# power.net
KiCad netlist of a schematic drawn in Altium Designer
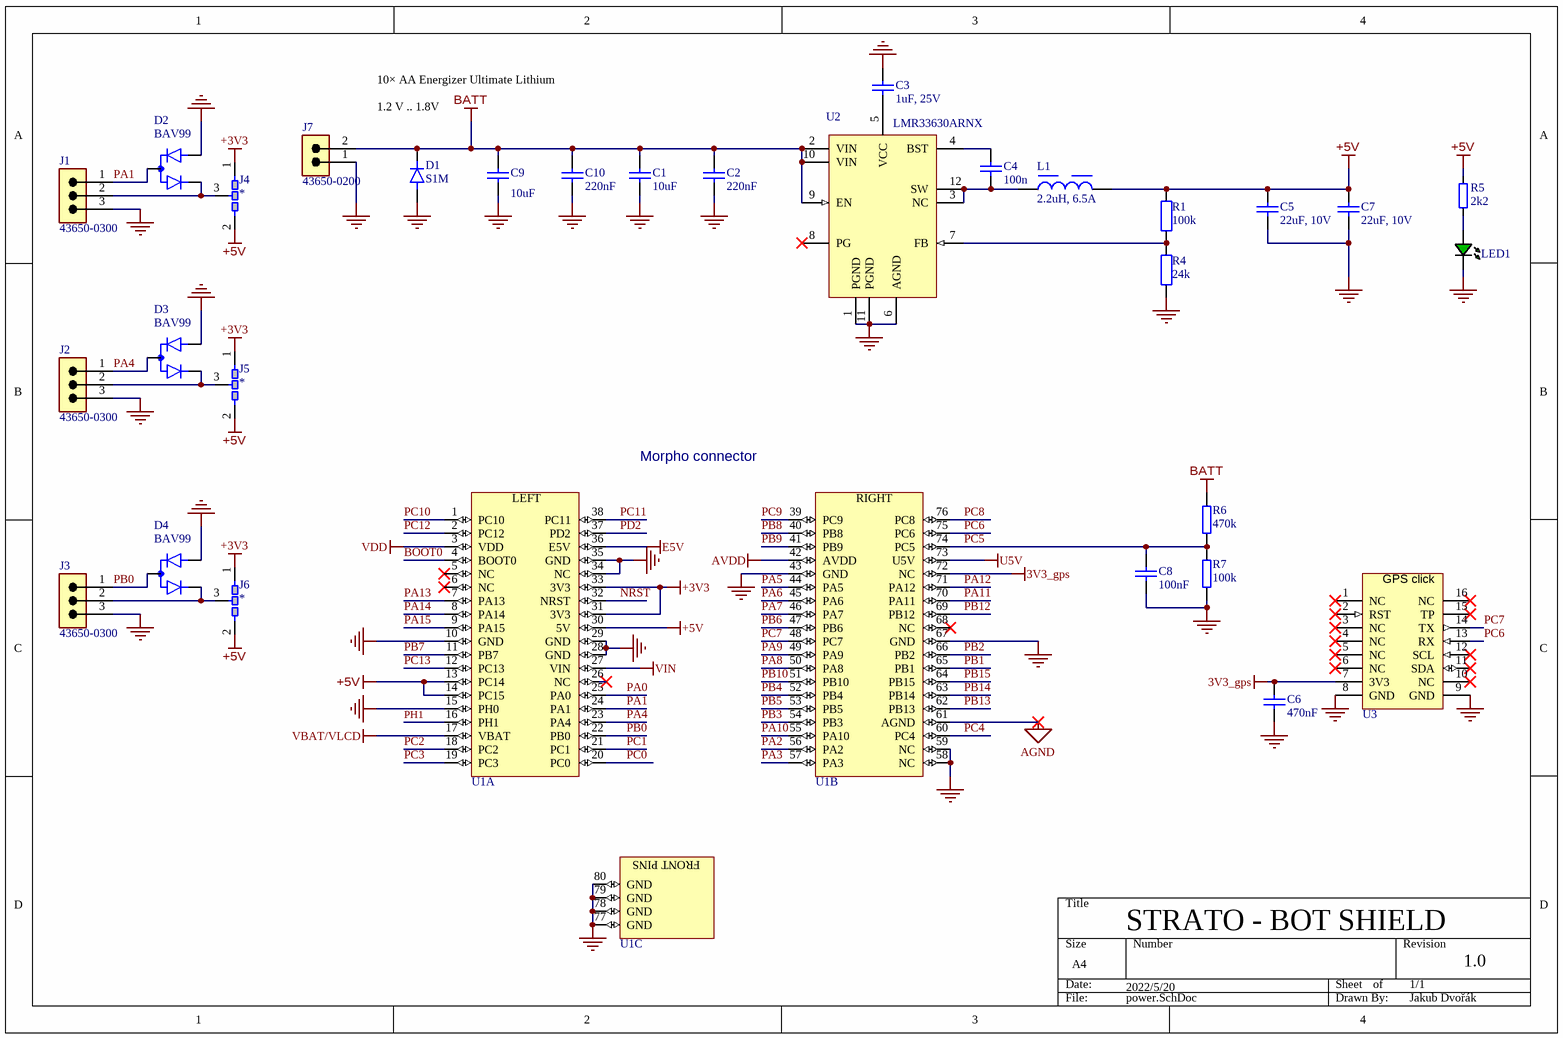
[diagram p0: power.SchDoc]

(export (version "E")
  (design (tool "Eeschema 10.0.6"))
  (components
    (comp (ref "C1")
      (value "10uF")
      (footprint "WCAP-CSGP_1206_L3.2W1.6H1.6")
      (description "WCAP-CSGP Multilayer Ceramic Chip Capacitor, General Purpose, size 1206, X5R, 10uF, 50V")
      (fields
        (field (name "MANUFACTURER") "Wurth Elektronik")
        (field (name "MANUFACTURER PART NUMBER") "885012108022")
      )
      (libsource (lib "Altium_WCAP-CSGP (rev22a)") (part "885012108022"))
    )
    (comp (ref "C2")
      (value "220nF")
      (footprint "WCAP-CSGP_0603_L1.6W0.8H0.8_Reflow")
      (description "WCAP-CSGP Multilayer Ceramic Chip Capacitor, General Purpose, size 0603, X7R, 220nF, 50V")
      (fields
        (field (name "MANUFACTURER") "Wurth Elektronik")
        (field (name "MANUFACTURER PART NUMBER") "885012206125")
      )
      (libsource (lib "Altium_WCAP-CSGP (rev22a)") (part "885012206125"))
    )
    (comp (ref "C3")
      (value "1uF, 25V")
      (footprint "WCAP-CSGP_0603_L1.6W0.8H0.8_Reflow")
      (description "WCAP-CSGP Multilayer Ceramic Chip Capacitor, General Purpose, size 0603, X7R, 1uF, 25V")
      (fields
        (field (name "MANUFACTURER") "Wurth Elektronik")
        (field (name "MANUFACTURER PART NUMBER") "885012206076")
      )
      (libsource (lib "Altium_WCAP-CSGP (rev22a)") (part "885012206076"))
    )
    (comp (ref "C4")
      (value "100n")
      (footprint "WCAP-CSGP_0603_L1.6W0.8H0.8_Reflow")
      (description "WCAP-CSGP Multilayer Ceramic Chip Capacitor, General Purpose, size 0603, X7R, 100nF, 25V")
      (fields
        (field (name "MANUFACTURER") "Wurth Elektronik")
        (field (name "MANUFACTURER PART NUMBER") "885012206071R")
      )
      (libsource (lib "Altium_WCAP-CSGP (rev22a)") (part "885012206071R"))
    )
    (comp (ref "C5")
      (value "22uF, 10V")
      (footprint "WCAP-CSGP_0805_L2W1.25H1.25")
      (description "WCAP-CSGP Multilayer Ceramic Chip Capacitor, General Purpose, size 0805, X5R, 22uF, 10V")
      (fields
        (field (name "MANUFACTURER") "Wurth Elektronik")
        (field (name "MANUFACTURER PART NUMBER") "885012107011")
      )
      (libsource (lib "Altium_WCAP-CSGP (rev22a)") (part "885012107011"))
    )
    (comp (ref "C6")
      (value "470nF")
      (footprint "WCAP-CSGP_0805_L2W1.25H1.25")
      (description "WCAP-CSGP Multilayer Ceramic Chip Capacitor, General Purpose, size 0805, X7R, 470nF, 50V")
      (fields
        (field (name "MANUFACTURER") "Wurth Elektronik")
        (field (name "MANUFACTURER PART NUMBER") "885012207102")
      )
      (libsource (lib "Altium_WCAP-CSGP (rev22a)") (part "885012207102"))
    )
    (comp (ref "C7")
      (value "22uF, 10V")
      (footprint "WCAP-CSGP_0805_L2W1.25H1.25")
      (description "WCAP-CSGP Multilayer Ceramic Chip Capacitor, General Purpose, size 0805, X5R, 22uF, 10V")
      (fields
        (field (name "MANUFACTURER") "Wurth Elektronik")
        (field (name "MANUFACTURER PART NUMBER") "885012107011")
      )
      (libsource (lib "Altium_WCAP-CSGP (rev22a)") (part "885012107011"))
    )
    (comp (ref "C8")
      (value "100nF")
      (footprint "WCAP-CSGP_0805_L2W1.25H0.8_Reflow")
      (description "WCAP-CSGP Multilayer Ceramic Chip Capacitor, General Purpose, size 0805, X7R, 100nF, 50V")
      (fields
        (field (name "MANUFACTURER") "Wurth Elektronik")
        (field (name "MANUFACTURER PART NUMBER") "885012207098R")
      )
      (libsource (lib "Altium_WCAP-CSGP (rev22a)") (part "885012207098R"))
    )
    (comp (ref "C9")
      (value "10uF")
      (footprint "WCAP-CSGP_1206_L3.2W1.6H1.6")
      (description "WCAP-CSGP Multilayer Ceramic Chip Capacitor, General Purpose, size 1206, X5R, 10uF, 50V")
      (fields
        (field (name "MANUFACTURER") "Wurth Elektronik")
        (field (name "MANUFACTURER PART NUMBER") "885012108022")
      )
      (libsource (lib "Altium_WCAP-CSGP (rev22a)") (part "885012108022"))
    )
    (comp (ref "C10")
      (value "220nF")
      (footprint "WCAP-CSGP_0603_L1.6W0.8H0.8_Reflow")
      (description "WCAP-CSGP Multilayer Ceramic Chip Capacitor, General Purpose, size 0603, X7R, 220nF, 50V")
      (fields
        (field (name "MANUFACTURER") "Wurth Elektronik")
        (field (name "MANUFACTURER PART NUMBER") "885012206125")
      )
      (libsource (lib "Altium_WCAP-CSGP (rev22a)") (part "885012206125"))
    )
    (comp (ref "D1")
      (value "S1M")
      (footprint "DIOM5127X23N(SMA)")
      (description "D; Si; 1000V; 1A; 1x;")
      (libsource (lib "altium_sql") (part "D"))
    )
    (comp (ref "D2")
      (value "BAV99")
      (footprint "SOT95P230X110-3N(SOT23)")
      (libsource (lib "Kubikova integrovana knihovna ") (part "BAV99"))
    )
    (comp (ref "D3")
      (value "BAV99")
      (footprint "SOT95P230X110-3N(SOT23)")
      (libsource (lib "Kubikova integrovana knihovna ") (part "BAV99"))
    )
    (comp (ref "D4")
      (value "BAV99")
      (footprint "SOT95P230X110-3N(SOT23)")
      (libsource (lib "Kubikova integrovana knihovna ") (part "BAV99"))
    )
    (comp (ref "J1")
      (value "43650-0300")
      (footprint "MOLEX_43650-0300")
      (description "Con; Micro Fit 3.0; 3x; PCB; Right angle; 250V; 5A; Male; Tin; ??;")
      (fields (field (name "MANUFACTURER") "Molex: 436500300"))
      (libsource (lib "altium_sql") (part "EJ_3PIN_MALE"))
    )
    (comp (ref "J2")
      (value "43650-0300")
      (footprint "MOLEX_43650-0300")
      (description "Con; Micro Fit 3.0; 3x; PCB; Right angle; 250V; 5A; Male; Tin; ??;")
      (fields (field (name "MANUFACTURER") "Molex: 436500300"))
      (libsource (lib "altium_sql") (part "EJ_3PIN_MALE"))
    )
    (comp (ref "J3")
      (value "43650-0300")
      (footprint "MOLEX_43650-0300")
      (description "Con; Micro Fit 3.0; 3x; PCB; Right angle; 250V; 5A; Male; Tin; ??;")
      (fields (field (name "MANUFACTURER") "Molex: 436500300"))
      (libsource (lib "altium_sql") (part "EJ_3PIN_MALE"))
    )
    (comp (ref "J4")
      (value "*")
      (footprint "JUMPER3_SMT_1LAYER")
      (description "Soldering Jumper, 3 Pins")
      (fields (field (name "AUTHOR") "JM 1.9.2015"))
      (libsource (lib "Production_Library") (part "JUMPER_3P"))
    )
    (comp (ref "J5")
      (value "*")
      (footprint "JUMPER3_SMT_1LAYER")
      (description "Soldering Jumper, 3 Pins")
      (fields (field (name "AUTHOR") "JM 1.9.2015"))
      (libsource (lib "Production_Library") (part "JUMPER_3P"))
    )
    (comp (ref "J6")
      (value "*")
      (footprint "JUMPER3_SMT_1LAYER")
      (description "Soldering Jumper, 3 Pins")
      (fields (field (name "AUTHOR") "JM 1.9.2015"))
      (libsource (lib "Production_Library") (part "JUMPER_3P"))
    )
    (comp (ref "J7")
      (value "43650-0200")
      (footprint "MOLEX_43650-0200")
      (description "Con; Micro Fit 3.0; 2x; PCB; Right angle; 600V; 5A; Male; Nickel; ??;")
      (fields (field (name "MANUFACTURER") "MOLEX: 43650-0200"))
      (libsource (lib "altium_sql") (part "EJ_2PIN_MALE"))
    )
    (comp (ref "L1")
      (value "2.2uH, 6.5A")
      (footprint "WE-LHMI_7030")
      (description "WE-LHMI SMT Power Inductor, size 7030, 2.2uH, 6.5A")
      (fields
        (field (name "MANUFACTURER") "Wurth Elektronik")
        (field (name "MANUFACTURER PART NUMBER") "74437346022")
      )
      (libsource (lib "ind-WE-LHMI (rev21a)") (part "74437346022"))
    )
    (comp (ref "LED1")
      (value "green")
      (footprint "0805LEDG")
      (libsource (lib "all_in_one_library") (part "LEDG_0805"))
    )
    (comp (ref "R1")
      (value "100k")
      (footprint "RES_0603")
      (description "100000.00")
      (fields (field (name "Comment") "Thick film"))
      (libsource (lib "all_in_one_library") (part "RES_100k_5%_0603"))
    )
    (comp (ref "R4")
      (value "24k")
      (footprint "RES_0603")
      (description "24000.00")
      (fields (field (name "Comment") "Thick film"))
      (libsource (lib "all_in_one_library") (part "RES_24k_5%_0603"))
    )
    (comp (ref "R5")
      (value "2k2")
      (footprint "RES_0603")
      (description "2200.00")
      (fields (field (name "Comment") "Thick film"))
      (libsource (lib "all_in_one_library") (part "RES_2k2_5%_0603"))
    )
    (comp (ref "R6")
      (value "470k")
      (footprint "RESC2012X06N(SMR0805)")
      (description "R; 470k; 0.125W; 1%; 150V; Thick Film; ±100ppm/K; 1x;")
      (libsource (lib "altium_sql") (part "R"))
    )
    (comp (ref "R7")
      (value "100k")
      (footprint "RESC2012X06N(SMR0805)")
      (description "R; 100k; 0.125W; 1%; 150V; Thick Film; ±100ppm/K; 1x;")
      (fields (field (name "MANUFACTURER") "YAGEO: RC0805FR-10100KL"))
      (libsource (lib "altium_sql") (part "R"))
    )
    (comp (ref "U1")
      (value "NUCLEO F466 MORPHO LEFT")
      (footprint "Nucleo_bot_pads")
      (libsource (lib "Kubikova ultra knihovna") (part "NUCLEO F466 MORPHO LEFT"))
    )
    (comp (ref "U2")
      (value "LMR33630ARNX")
      (footprint "QFN50P200X300X100-12N")
      (description "IC; SMPS Regulator/Controller; 3.8V; 36V; 1x;")
      (fields
        (field (name "MANUFACTURER") "Texas Instruments: LMR33630ARNXR;;Texas Instruments: LMR33630ARNXT")
      )
      (libsource (lib "altium_sql") (part "EU+LMR33630ARNXXX0"))
    )
    (comp (ref "U3")
      (value "GPS Click")
      (footprint "GPS click - no legs")
      (libsource (lib "Kubikova ultra knihovna") (part "GPS Click"))
    )
  )
  (nets
    (net (code "1") (name "+3V3") (class "Default")
      (node (ref "J4") (pin "1") (pinfunction "1_1") (pintype "passive"))
      (node (ref "J5") (pin "1") (pinfunction "1_1") (pintype "passive"))
      (node (ref "J6") (pin "1") (pinfunction "1_1") (pintype "passive"))
      (node (ref "U1") (pin "31") (pinfunction "3V3_31") (pintype "bidirectional"))
      (node (ref "U1") (pin "33") (pinfunction "3V3_33") (pintype "bidirectional"))
    )
    (net (code "2") (name "+5V") (class "Default")
      (node (ref "C5") (pin "2") (pinfunction "2_2") (pintype "passive"))
      (node (ref "C7") (pin "2") (pinfunction "2_2") (pintype "passive"))
      (node (ref "J4") (pin "2") (pinfunction "2_2") (pintype "passive"))
      (node (ref "J5") (pin "2") (pinfunction "2_2") (pintype "passive"))
      (node (ref "J6") (pin "2") (pinfunction "2_2") (pintype "passive"))
      (node (ref "L1") (pin "2") (pinfunction "2_2") (pintype "passive"))
      (node (ref "R1") (pin "2") (pinfunction "2_2") (pintype "passive"))
      (node (ref "R5") (pin "2") (pinfunction "2_2") (pintype "passive"))
      (node (ref "U1") (pin "13") (pinfunction "PC14_13") (pintype "bidirectional"))
      (node (ref "U1") (pin "14") (pinfunction "PC15_14") (pintype "bidirectional"))
      (node (ref "U1") (pin "30") (pinfunction "5V_30") (pintype "bidirectional"))
    )
    (net (code "3") (name "/BOOT0") (class "Default")
      (node (ref "U1") (pin "4") (pinfunction "BOOT0_4") (pintype "bidirectional"))
    )
    (net (code "4") (name "/NRST") (class "Default")
      (node (ref "U1") (pin "32") (pinfunction "NRST_32") (pintype "bidirectional"))
    )
    (net (code "5") (name "/PA0") (class "Default")
      (node (ref "U1") (pin "25") (pinfunction "PA0_25") (pintype "bidirectional"))
    )
    (net (code "6") (name "/PA1") (class "Default")
      (node (ref "D2") (pin "3") (pinfunction "C1A2_3") (pintype "passive"))
      (node (ref "J1") (pin "1") (pinfunction "1_1") (pintype "passive"))
      (node (ref "U1") (pin "24") (pinfunction "PA1_24") (pintype "bidirectional"))
    )
    (net (code "7") (name "/PA2") (class "Default")
      (node (ref "U1") (pin "56") (pinfunction "PA2_56") (pintype "bidirectional"))
    )
    (net (code "8") (name "/PA3") (class "Default")
      (node (ref "U1") (pin "57") (pinfunction "PA3_57") (pintype "bidirectional"))
    )
    (net (code "9") (name "/PA4") (class "Default")
      (node (ref "D3") (pin "3") (pinfunction "C1A2_3") (pintype "passive"))
      (node (ref "J2") (pin "1") (pinfunction "1_1") (pintype "passive"))
      (node (ref "U1") (pin "23") (pinfunction "PA4_23") (pintype "bidirectional"))
    )
    (net (code "10") (name "/PA5") (class "Default")
      (node (ref "U1") (pin "44") (pinfunction "PA5_44") (pintype "bidirectional"))
    )
    (net (code "11") (name "/PA6") (class "Default")
      (node (ref "U1") (pin "45") (pinfunction "PA6_45") (pintype "bidirectional"))
    )
    (net (code "12") (name "/PA7") (class "Default")
      (node (ref "U1") (pin "46") (pinfunction "PA7_46") (pintype "bidirectional"))
    )
    (net (code "13") (name "/PA8") (class "Default")
      (node (ref "U1") (pin "50") (pinfunction "PA8_50") (pintype "bidirectional"))
    )
    (net (code "14") (name "/PA9") (class "Default")
      (node (ref "U1") (pin "49") (pinfunction "PA9_49") (pintype "bidirectional"))
    )
    (net (code "15") (name "/PA10") (class "Default")
      (node (ref "U1") (pin "55") (pinfunction "PA10_55") (pintype "bidirectional"))
    )
    (net (code "16") (name "/PA11") (class "Default")
      (node (ref "U1") (pin "70") (pinfunction "PA11_70") (pintype "bidirectional"))
    )
    (net (code "17") (name "/PA12") (class "Default")
      (node (ref "U1") (pin "71") (pinfunction "PA12_71") (pintype "bidirectional"))
    )
    (net (code "18") (name "/PA13") (class "Default")
      (node (ref "U1") (pin "7") (pinfunction "PA13_7") (pintype "bidirectional"))
    )
    (net (code "19") (name "/PA14") (class "Default")
      (node (ref "U1") (pin "8") (pinfunction "PA14_8") (pintype "bidirectional"))
    )
    (net (code "20") (name "/PA15") (class "Default")
      (node (ref "U1") (pin "9") (pinfunction "PA15_9") (pintype "bidirectional"))
    )
    (net (code "21") (name "/PB0") (class "Default")
      (node (ref "D4") (pin "3") (pinfunction "C1A2_3") (pintype "passive"))
      (node (ref "J3") (pin "1") (pinfunction "1_1") (pintype "passive"))
      (node (ref "U1") (pin "22") (pinfunction "PB0_22") (pintype "bidirectional"))
    )
    (net (code "22") (name "/PB1") (class "Default")
      (node (ref "U1") (pin "65") (pinfunction "PB1_65") (pintype "bidirectional"))
    )
    (net (code "23") (name "/PB2") (class "Default")
      (node (ref "U1") (pin "66") (pinfunction "PB2_66") (pintype "bidirectional"))
    )
    (net (code "24") (name "/PB3") (class "Default")
      (node (ref "U1") (pin "54") (pinfunction "PB3_54") (pintype "bidirectional"))
    )
    (net (code "25") (name "/PB4") (class "Default")
      (node (ref "U1") (pin "52") (pinfunction "PB4_52") (pintype "bidirectional"))
    )
    (net (code "26") (name "/PB5") (class "Default")
      (node (ref "U1") (pin "53") (pinfunction "PB5_53") (pintype "bidirectional"))
    )
    (net (code "27") (name "/PB6") (class "Default")
      (node (ref "U1") (pin "47") (pinfunction "PB6_47") (pintype "bidirectional"))
    )
    (net (code "28") (name "/PB7") (class "Default")
      (node (ref "U1") (pin "11") (pinfunction "PB7_11") (pintype "bidirectional"))
    )
    (net (code "29") (name "/PB8") (class "Default")
      (node (ref "U1") (pin "40") (pinfunction "PB8_40") (pintype "bidirectional"))
    )
    (net (code "30") (name "/PB9") (class "Default")
      (node (ref "U1") (pin "41") (pinfunction "PB9_41") (pintype "bidirectional"))
    )
    (net (code "31") (name "/PB10") (class "Default")
      (node (ref "U1") (pin "51") (pinfunction "PB10_51") (pintype "bidirectional"))
    )
    (net (code "32") (name "/PB12") (class "Default")
      (node (ref "U1") (pin "69") (pinfunction "PB12_69") (pintype "bidirectional"))
    )
    (net (code "33") (name "/PB13") (class "Default")
      (node (ref "U1") (pin "62") (pinfunction "PB13_62") (pintype "bidirectional"))
    )
    (net (code "34") (name "/PB14") (class "Default")
      (node (ref "U1") (pin "63") (pinfunction "PB14_63") (pintype "bidirectional"))
    )
    (net (code "35") (name "/PB15") (class "Default")
      (node (ref "U1") (pin "64") (pinfunction "PB15_64") (pintype "bidirectional"))
    )
    (net (code "36") (name "/PC0") (class "Default")
      (node (ref "U1") (pin "20") (pinfunction "PC0_20") (pintype "bidirectional"))
    )
    (net (code "37") (name "/PC1") (class "Default")
      (node (ref "U1") (pin "21") (pinfunction "PC1_21") (pintype "bidirectional"))
    )
    (net (code "38") (name "/PC2") (class "Default")
      (node (ref "U1") (pin "18") (pinfunction "PC2_18") (pintype "bidirectional"))
    )
    (net (code "39") (name "/PC3") (class "Default")
      (node (ref "U1") (pin "19") (pinfunction "PC3_19") (pintype "bidirectional"))
    )
    (net (code "40") (name "/PC4") (class "Default")
      (node (ref "U1") (pin "60") (pinfunction "PC4_60") (pintype "bidirectional"))
    )
    (net (code "41") (name "/PC5") (class "Default")
      (node (ref "C8") (pin "2") (pinfunction "2_2") (pintype "passive"))
      (node (ref "R6") (pin "1") (pinfunction "1_1") (pintype "passive"))
      (node (ref "R7") (pin "2") (pinfunction "2_2") (pintype "passive"))
      (node (ref "U1") (pin "74") (pinfunction "PC5_74") (pintype "bidirectional"))
    )
    (net (code "42") (name "/PC6") (class "Default")
      (node (ref "U1") (pin "75") (pinfunction "PC6_75") (pintype "bidirectional"))
      (node (ref "U3") (pin "13") (pinfunction "RX_13") (pintype "input"))
    )
    (net (code "43") (name "/PC7") (class "Default")
      (node (ref "U1") (pin "48") (pinfunction "PC7_48") (pintype "bidirectional"))
      (node (ref "U3") (pin "14") (pinfunction "TX_14") (pintype "output"))
    )
    (net (code "44") (name "/PC8") (class "Default")
      (node (ref "U1") (pin "76") (pinfunction "PC8_76") (pintype "bidirectional"))
    )
    (net (code "45") (name "/PC9") (class "Default")
      (node (ref "U1") (pin "39") (pinfunction "PC9_39") (pintype "bidirectional"))
    )
    (net (code "46") (name "/PC10") (class "Default")
      (node (ref "U1") (pin "1") (pinfunction "PC10_1") (pintype "bidirectional"))
    )
    (net (code "47") (name "/PC11") (class "Default")
      (node (ref "U1") (pin "38") (pinfunction "PC11_38") (pintype "bidirectional"))
    )
    (net (code "48") (name "/PC12") (class "Default")
      (node (ref "U1") (pin "2") (pinfunction "PC12_2") (pintype "bidirectional"))
    )
    (net (code "49") (name "/PC13") (class "Default")
      (node (ref "U1") (pin "12") (pinfunction "PC13_12") (pintype "bidirectional"))
    )
    (net (code "50") (name "/PD2") (class "Default")
      (node (ref "U1") (pin "37") (pinfunction "PD2_37") (pintype "bidirectional"))
    )
    (net (code "51") (name "/PH1") (class "Default")
      (node (ref "U1") (pin "16") (pinfunction "PH1_16") (pintype "bidirectional"))
    )
    (net (code "52") (name "3V3_gps") (class "Default")
      (node (ref "C6") (pin "2") (pinfunction "2_2") (pintype "passive"))
      (node (ref "U1") (pin "72") (pinfunction "NC_72") (pintype "bidirectional"))
      (node (ref "U3") (pin "7") (pinfunction "3V3_7") (pintype "power_in"))
    )
    (net (code "53") (name "AGND") (class "Default")
      (node (ref "U1") (pin "61") (pinfunction "AGND_61") (pintype "bidirectional"))
    )
    (net (code "54") (name "AVDD") (class "Default")
      (node (ref "U1") (pin "42") (pinfunction "AVDD_42") (pintype "bidirectional"))
    )
    (net (code "55") (name "BATT") (class "Default")
      (node (ref "C1") (pin "2") (pinfunction "2_2") (pintype "passive"))
      (node (ref "C10") (pin "2") (pinfunction "2_2") (pintype "passive"))
      (node (ref "C2") (pin "2") (pinfunction "2_2") (pintype "passive"))
      (node (ref "C9") (pin "2") (pinfunction "2_2") (pintype "passive"))
      (node (ref "D1") (pin "1") (pinfunction "C_1") (pintype "passive"))
      (node (ref "J7") (pin "2") (pinfunction "2_2") (pintype "passive"))
      (node (ref "R6") (pin "2") (pinfunction "2_2") (pintype "passive"))
      (node (ref "U2") (pin "10") (pinfunction "VIN_10") (pintype "power_in"))
      (node (ref "U2") (pin "2") (pinfunction "VIN_2") (pintype "power_in"))
      (node (ref "U2") (pin "9") (pinfunction "EN_9") (pintype "input"))
    )
    (net (code "56") (name "E5V") (class "Default")
      (node (ref "U1") (pin "36") (pinfunction "E5V_36") (pintype "bidirectional"))
    )
    (net (code "57") (name "GND") (class "Default")
      (node (ref "C1") (pin "1") (pinfunction "1_1") (pintype "passive"))
      (node (ref "C10") (pin "1") (pinfunction "1_1") (pintype "passive"))
      (node (ref "C2") (pin "1") (pinfunction "1_1") (pintype "passive"))
      (node (ref "C3") (pin "2") (pinfunction "2_2") (pintype "passive"))
      (node (ref "C5") (pin "1") (pinfunction "1_1") (pintype "passive"))
      (node (ref "C6") (pin "1") (pinfunction "1_1") (pintype "passive"))
      (node (ref "C7") (pin "1") (pinfunction "1_1") (pintype "passive"))
      (node (ref "C8") (pin "1") (pinfunction "1_1") (pintype "passive"))
      (node (ref "C9") (pin "1") (pinfunction "1_1") (pintype "passive"))
      (node (ref "D1") (pin "2") (pinfunction "A_2") (pintype "passive"))
      (node (ref "D2") (pin "1") (pinfunction "A1_1") (pintype "passive"))
      (node (ref "D3") (pin "1") (pinfunction "A1_1") (pintype "passive"))
      (node (ref "D4") (pin "1") (pinfunction "A1_1") (pintype "passive"))
      (node (ref "J1") (pin "3") (pinfunction "3_3") (pintype "passive"))
      (node (ref "J2") (pin "3") (pinfunction "3_3") (pintype "passive"))
      (node (ref "J3") (pin "3") (pinfunction "3_3") (pintype "passive"))
      (node (ref "J7") (pin "1") (pinfunction "1_1") (pintype "passive"))
      (node (ref "LED1") (pin "K") (pinfunction "K_K") (pintype "passive"))
      (node (ref "R4") (pin "1") (pinfunction "1_1") (pintype "passive"))
      (node (ref "R7") (pin "1") (pinfunction "1_1") (pintype "passive"))
      (node (ref "U1") (pin "10") (pinfunction "GND_10") (pintype "bidirectional"))
      (node (ref "U1") (pin "15") (pinfunction "PH0_15") (pintype "bidirectional"))
      (node (ref "U1") (pin "28") (pinfunction "GND_28") (pintype "bidirectional"))
      (node (ref "U1") (pin "29") (pinfunction "GND_29") (pintype "bidirectional"))
      (node (ref "U1") (pin "34") (pinfunction "NC_34") (pintype "bidirectional"))
      (node (ref "U1") (pin "35") (pinfunction "GND_35") (pintype "bidirectional"))
      (node (ref "U1") (pin "43") (pinfunction "GND_43") (pintype "bidirectional"))
      (node (ref "U1") (pin "58") (pinfunction "NC_58") (pintype "bidirectional"))
      (node (ref "U1") (pin "59") (pinfunction "NC_59") (pintype "bidirectional"))
      (node (ref "U1") (pin "67") (pinfunction "GND_67") (pintype "bidirectional"))
      (node (ref "U1") (pin "77") (pinfunction "GND_77") (pintype "bidirectional"))
      (node (ref "U1") (pin "78") (pinfunction "GND_78") (pintype "bidirectional"))
      (node (ref "U1") (pin "79") (pinfunction "GND_79") (pintype "bidirectional"))
      (node (ref "U1") (pin "80") (pinfunction "GND_80") (pintype "bidirectional"))
      (node (ref "U2") (pin "1") (pinfunction "PGND_1") (pintype "power_in"))
      (node (ref "U2") (pin "11") (pinfunction "PGND_11") (pintype "power_in"))
      (node (ref "U2") (pin "6") (pinfunction "AGND_6") (pintype "power_in"))
      (node (ref "U3") (pin "8") (pinfunction "GND_8") (pintype "power_in"))
      (node (ref "U3") (pin "9") (pinfunction "GND_9") (pintype "power_in"))
    )
    (net (code "58") (name "Net-(D2-C2)") (class "Default")
      (node (ref "D2") (pin "2") (pinfunction "C2_2") (pintype "passive"))
      (node (ref "J1") (pin "2") (pinfunction "2_2") (pintype "passive"))
      (node (ref "J4") (pin "3") (pinfunction "3_3") (pintype "passive"))
    )
    (net (code "59") (name "Net-(D3-C2)") (class "Default")
      (node (ref "D3") (pin "2") (pinfunction "C2_2") (pintype "passive"))
      (node (ref "J2") (pin "2") (pinfunction "2_2") (pintype "passive"))
      (node (ref "J5") (pin "3") (pinfunction "3_3") (pintype "passive"))
    )
    (net (code "60") (name "Net-(D4-C2)") (class "Default")
      (node (ref "D4") (pin "2") (pinfunction "C2_2") (pintype "passive"))
      (node (ref "J3") (pin "2") (pinfunction "2_2") (pintype "passive"))
      (node (ref "J6") (pin "3") (pinfunction "3_3") (pintype "passive"))
    )
    (net (code "61") (name "Net-(LED1-PadA)") (class "Default")
      (node (ref "LED1") (pin "A") (pinfunction "A_A") (pintype "passive"))
      (node (ref "R5") (pin "1") (pinfunction "1_1") (pintype "passive"))
    )
    (net (code "62") (name "Net-(U2-BST)") (class "Default")
      (node (ref "C4") (pin "2") (pinfunction "2_2") (pintype "passive"))
      (node (ref "U2") (pin "4") (pinfunction "BST_4") (pintype "passive"))
    )
    (net (code "63") (name "Net-(U2-FB)") (class "Default")
      (node (ref "R1") (pin "1") (pinfunction "1_1") (pintype "passive"))
      (node (ref "R4") (pin "2") (pinfunction "2_2") (pintype "passive"))
      (node (ref "U2") (pin "7") (pinfunction "FB_7") (pintype "input"))
    )
    (net (code "64") (name "Net-(U2-NC)") (class "Default")
      (node (ref "C4") (pin "1") (pinfunction "1_1") (pintype "passive"))
      (node (ref "L1") (pin "1") (pinfunction "1_1") (pintype "passive"))
      (node (ref "U2") (pin "12") (pinfunction "SW_12") (pintype "passive"))
      (node (ref "U2") (pin "3") (pinfunction "NC_3") (pintype "passive"))
    )
    (net (code "65") (name "Net-(U2-VCC)") (class "Default")
      (node (ref "C3") (pin "1") (pinfunction "1_1") (pintype "passive"))
      (node (ref "U2") (pin "5") (pinfunction "VCC_5") (pintype "power_in"))
    )
    (net (code "66") (name "U5V") (class "Default")
      (node (ref "U1") (pin "73") (pinfunction "U5V_73") (pintype "bidirectional"))
    )
    (net (code "67") (name "VBAT{slash}VLCD") (class "Default")
      (node (ref "U1") (pin "17") (pinfunction "VBAT_17") (pintype "bidirectional"))
    )
    (net (code "68") (name "VDD") (class "Default")
      (node (ref "U1") (pin "3") (pinfunction "VDD_3") (pintype "bidirectional"))
    )
    (net (code "69") (name "VIN") (class "Default")
      (node (ref "U1") (pin "27") (pinfunction "VIN_27") (pintype "bidirectional"))
    )
    (net (code "70") (name "unconnected-(U1A-NC-Pad5)") (class "Default")
      (node (ref "U1") (pin "5") (pinfunction "NC_5") (pintype "bidirectional+no_connect"))
    )
    (net (code "71") (name "unconnected-(U1A-NC-Pad6)") (class "Default")
      (node (ref "U1") (pin "6") (pinfunction "NC_6") (pintype "bidirectional+no_connect"))
    )
    (net (code "72") (name "unconnected-(U1A-NC-Pad26)") (class "Default")
      (node (ref "U1") (pin "26") (pinfunction "NC_26") (pintype "bidirectional+no_connect"))
    )
    (net (code "73") (name "unconnected-(U1B-NC-Pad68)") (class "Default")
      (node (ref "U1") (pin "68") (pinfunction "NC_68") (pintype "bidirectional+no_connect"))
    )
    (net (code "74") (name "unconnected-(U2-PG-Pad8)") (class "Default")
      (node (ref "U2") (pin "8") (pinfunction "PG_8") (pintype "open_collector+no_connect"))
    )
    (net (code "75") (name "unconnected-(U3-NC-Pad1)") (class "Default")
      (node (ref "U3") (pin "1") (pinfunction "NC_1") (pintype "tri_state+no_connect"))
    )
    (net (code "76") (name "unconnected-(U3-NC-Pad3)") (class "Default")
      (node (ref "U3") (pin "3") (pinfunction "NC_3") (pintype "tri_state+no_connect"))
    )
    (net (code "77") (name "unconnected-(U3-NC-Pad4)") (class "Default")
      (node (ref "U3") (pin "4") (pinfunction "NC_4") (pintype "tri_state+no_connect"))
    )
    (net (code "78") (name "unconnected-(U3-NC-Pad5)") (class "Default")
      (node (ref "U3") (pin "5") (pinfunction "NC_5") (pintype "tri_state+no_connect"))
    )
    (net (code "79") (name "unconnected-(U3-NC-Pad6)") (class "Default")
      (node (ref "U3") (pin "6") (pinfunction "NC_6") (pintype "tri_state+no_connect"))
    )
    (net (code "80") (name "unconnected-(U3-NC-Pad10)") (class "Default")
      (node (ref "U3") (pin "10") (pinfunction "NC_10") (pintype "open_emitter+no_connect"))
    )
    (net (code "81") (name "unconnected-(U3-NC-Pad16)") (class "Default")
      (node (ref "U3") (pin "16") (pinfunction "NC_16") (pintype "tri_state+no_connect"))
    )
    (net (code "82") (name "unconnected-(U3-RST-Pad2)") (class "Default")
      (node (ref "U3") (pin "2") (pinfunction "RST_2") (pintype "input+no_connect"))
    )
    (net (code "83") (name "unconnected-(U3-SCL-Pad12)") (class "Default")
      (node (ref "U3") (pin "12") (pinfunction "SCL_12") (pintype "input+no_connect"))
    )
    (net (code "84") (name "unconnected-(U3-SDA-Pad11)") (class "Default")
      (node (ref "U3") (pin "11") (pinfunction "SDA_11") (pintype "bidirectional+no_connect"))
    )
    (net (code "85") (name "unconnected-(U3-TP-Pad15)") (class "Default")
      (node (ref "U3") (pin "15") (pinfunction "TP_15") (pintype "tri_state+no_connect"))
    )
  )
)
